# SCH_Altium_OpenComs_APSM1_2023-05-12.net
KiCad netlist of a schematic drawn in Altium Designer
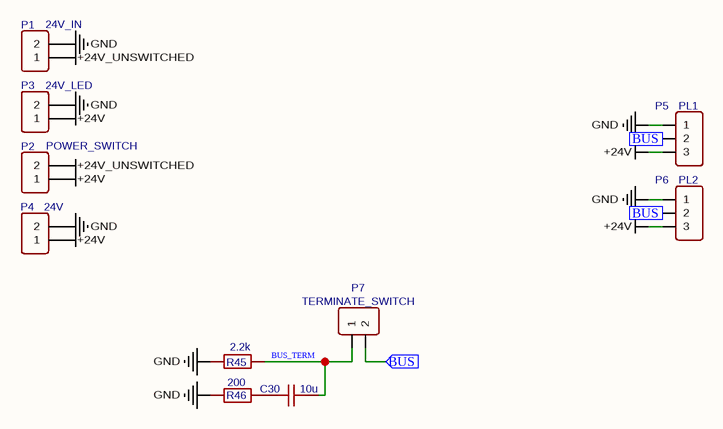
[diagram p0: SCH_Altium_OpenComs_APSM1_2023-05-12.schdoc]

(export (version "E")
  (design (tool "Eeschema 10.0.6"))
  (components
    (comp (ref "C30")
      (value "10u")
      (fields
        (field (name "BOM_SUPPLIER PART") "C13585")
        (field (name "BOM_MANUFACTURER PART") "CL31A106KBHNNNE")
        (field (name "CONTRIBUTOR") "LCEDA_Lib")
      )
      (libsource (lib "altium-import") (part "root_0_10u_"))
    )
    (comp (ref "P1")
      (value "24V_IN")
      (fields (field (name "CONTRIBUTOR") "LCEDA_Lib"))
      (libsource (lib "altium-import") (part "root_2_24V_IN_"))
    )
    (comp (ref "P2")
      (value "POWER_SWITCH")
      (fields (field (name "CONTRIBUTOR") "LCEDA_Lib"))
      (libsource (lib "altium-import") (part "root_2_POWER_SWITCH_"))
    )
    (comp (ref "P3")
      (value "24V_LED")
      (fields (field (name "CONTRIBUTOR") "LCEDA_Lib"))
      (libsource (lib "altium-import") (part "root_2_24V_LED_"))
    )
    (comp (ref "P4")
      (value "24V")
      (fields (field (name "CONTRIBUTOR") "LCEDA_Lib"))
      (libsource (lib "altium-import") (part "root_2_24V_"))
    )
    (comp (ref "P5")
      (value "PL1")
      (fields (field (name "CONTRIBUTOR") "LCEDA_Lib"))
      (libsource (lib "altium-import") (part "root_0_PL1_"))
    )
    (comp (ref "P6")
      (value "PL2")
      (fields (field (name "CONTRIBUTOR") "LCEDA_Lib"))
      (libsource (lib "altium-import") (part "root_0_PL2_"))
    )
    (comp (ref "P7")
      (value "TERMINATE_SWITCH")
      (fields (field (name "CONTRIBUTOR") "LCEDA_Lib"))
      (libsource (lib "altium-import") (part "root_1_TERMINATE_SWITCH_"))
    )
    (comp (ref "R45")
      (value "2.2k")
      (fields
        (field (name "BOM_SUPPLIER PART") "C17520")
        (field (name "BOM_MANUFACTURER PART") "0805W8F2201T5E")
        (field (name "CONTRIBUTOR") "LCEDA_Lib")
      )
      (libsource (lib "altium-import") (part "root_0_2.2k_"))
    )
    (comp (ref "R46")
      (value "200")
      (fields
        (field (name "BOM_SUPPLIER PART") "C17540")
        (field (name "BOM_MANUFACTURER PART") "0805W8F2000T5E")
        (field (name "CONTRIBUTOR") "LCEDA_Lib")
      )
      (libsource (lib "altium-import") (part "root_2_200_"))
    )
  )
  (nets
    (net (code "1") (name "+24V") (class "Default")
      (node (ref "P2") (pin "1") (pinfunction "1_1") (pintype "passive"))
      (node (ref "P3") (pin "1") (pinfunction "1_1") (pintype "passive"))
      (node (ref "P4") (pin "1") (pinfunction "1_1") (pintype "passive"))
      (node (ref "P5") (pin "3") (pinfunction "3_3") (pintype "passive"))
      (node (ref "P6") (pin "3") (pinfunction "3_3") (pintype "passive"))
    )
    (net (code "2") (name "+24V_UNSWITCHED") (class "Default")
      (node (ref "P1") (pin "1") (pinfunction "1_1") (pintype "passive"))
      (node (ref "P2") (pin "2") (pinfunction "2_2") (pintype "passive"))
    )
    (net (code "3") (name "/BUS") (class "Default")
      (node (ref "P5") (pin "2") (pinfunction "2_2") (pintype "passive"))
      (node (ref "P6") (pin "2") (pinfunction "2_2") (pintype "passive"))
      (node (ref "P7") (pin "2") (pinfunction "2_2") (pintype "passive"))
    )
    (net (code "4") (name "/BUS_TERM") (class "Default")
      (node (ref "C30") (pin "2") (pinfunction "2_2") (pintype "passive"))
      (node (ref "P7") (pin "1") (pinfunction "1_1") (pintype "passive"))
      (node (ref "R45") (pin "2") (pinfunction "2_2") (pintype "passive"))
    )
    (net (code "5") (name "GND") (class "Default")
      (node (ref "P1") (pin "2") (pinfunction "2_2") (pintype "passive"))
      (node (ref "P3") (pin "2") (pinfunction "2_2") (pintype "passive"))
      (node (ref "P4") (pin "2") (pinfunction "2_2") (pintype "passive"))
      (node (ref "P5") (pin "1") (pinfunction "1_1") (pintype "passive"))
      (node (ref "P6") (pin "1") (pinfunction "1_1") (pintype "passive"))
      (node (ref "R45") (pin "1") (pinfunction "1_1") (pintype "passive"))
      (node (ref "R46") (pin "2") (pinfunction "2_2") (pintype "passive"))
    )
    (net (code "6") (name "Net-(C30-Pad1)") (class "Default")
      (node (ref "C30") (pin "1") (pinfunction "1_1") (pintype "passive"))
      (node (ref "R46") (pin "1") (pinfunction "1_1") (pintype "passive"))
    )
  )
)
